# USB_Battery_Charging.net
KiCad netlist of a schematic drawn in Altium Designer
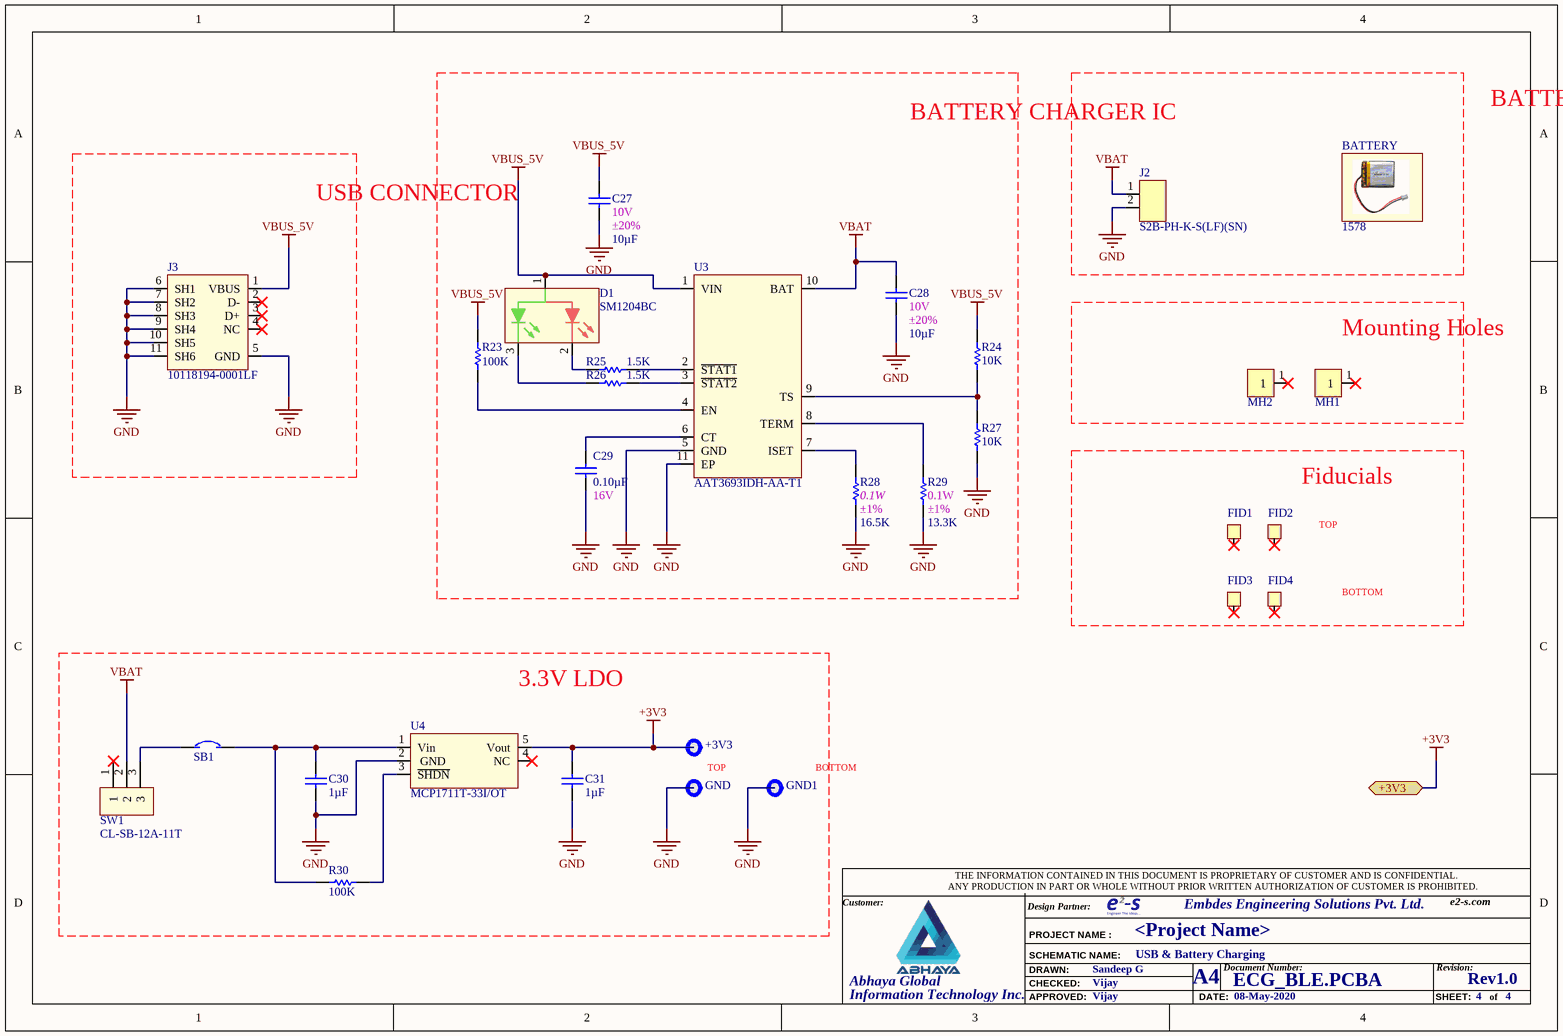
[diagram p0: USB & Battery Charging.SchDoc]

(export (version "E")
  (design (tool "Eeschema 10.0.6"))
  (components
    (comp (ref "+3V3")
      (value "TEST POINT")
      (footprint "TP_40X40")
      (fields (field (name "INTERNAL PART NUMBER") "EMS-TP40X40-S"))
      (libsource (lib "Integrated_Master_Library") (part "EMS-TP40X40-S"))
    )
    (comp (ref "BATTERY")
      (value "1578")
      (description "BATTERY LITHIUM 3.7V 500MAH")
      (fields
        (field (name "INTERNAL PART NUMBER") "EMS-1578")
        (field (name "MANUFACTURER") "Adafruit Industries LLC")
      )
      (libsource (lib "Master_ Library") (part "EMS-1578"))
    )
    (comp (ref "C27")
      (value "10µF")
      (footprint "SMDC0402")
      (description "CAP CER 10UF 10V X5R 0402")
      (fields
        (field (name "MANUFACTURER") "Samsung Electro-Mechanics America, Inc.")
        (field (name "MANUFACTURER PART NUMBER") "CL05A106MP5NUNC")
        (field (name "1ST AUXILIARY FIELD") "10V")
        (field (name "2ND AUXILIARY FIELD") "±20%")
      )
      (libsource (lib "Master_ Library") (part "ECA10U0M10V0-SB"))
    )
    (comp (ref "C28")
      (value "10µF")
      (footprint "SMDC0402")
      (description "CAP CER 10UF 10V X5R 0402")
      (fields
        (field (name "MANUFACTURER") "Samsung Electro-Mechanics America, Inc.")
        (field (name "MANUFACTURER PART NUMBER") "CL05A106MP5NUNC")
        (field (name "1ST AUXILIARY FIELD") "10V")
        (field (name "2ND AUXILIARY FIELD") "±20%")
      )
      (libsource (lib "Master_ Library") (part "ECA10U0M10V0-SB"))
    )
    (comp (ref "C29")
      (value "0.10µF")
      (footprint "SMDC0402")
      (description "CAP CER 0.1UF 16V X7R 0402")
      (fields
        (field (name "MANUFACTURER") "Samsung Electro-Mechanics America, Inc.")
        (field (name "MANUFACTURER PART NUMBER") "CL05B104KO5NNNC")
        (field (name "1ST AUXILIARY FIELD") "16V")
      )
      (libsource (lib "Master_ Library") (part "ECA0U10K16V0-1-SB"))
    )
    (comp (ref "C30")
      (value "1µF")
      (footprint "SMDC0402")
      (description "CAP CER 1UF 16V X5R 0402")
      (fields
        (field (name "MANUFACTURER") "Samsung Electro-Mechanics")
        (field (name "VENDOR PART NUMBER") "1276-1067-1-ND")
      )
      (libsource (lib "Integrated_Master_Library") (part "ECA1U00L16V0-SB"))
    )
    (comp (ref "C31")
      (value "1µF")
      (footprint "SMDC0402")
      (description "CAP CER 1UF 16V X5R 0402")
      (fields
        (field (name "MANUFACTURER") "Samsung Electro-Mechanics")
        (field (name "VENDOR PART NUMBER") "1276-1067-1-ND")
      )
      (libsource (lib "Integrated_Master_Library") (part "ECA1U00L16V0-SB"))
    )
    (comp (ref "D1")
      (value "SM1204BC")
      (footprint "LED-SM1204BC")
      (description "LED GREEN/RED CLEAR 1204 SMD R/A")
      (fields (field (name "MANUFACTURER") "Bivar Inc.") (field (name "VENDOR PART NUMBER") "492-1228-1-ND"))
      (libsource (lib "ECG_BLE") (part "ELDGR2V0020M0-S"))
    )
    (comp (ref "FID1")
      (value "FID40X40")
      (footprint "FID40X40")
      (libsource (lib "Integrated_Master_Library") (part "FID_40X40"))
    )
    (comp (ref "FID2")
      (value "FID40X40")
      (footprint "FID40X40")
      (libsource (lib "Integrated_Master_Library") (part "FID_40X40"))
    )
    (comp (ref "FID3")
      (value "FID40X40")
      (footprint "FID40X40")
      (libsource (lib "Integrated_Master_Library") (part "FID_40X40"))
    )
    (comp (ref "FID4")
      (value "FID40X40")
      (footprint "FID40X40")
      (libsource (lib "Integrated_Master_Library") (part "FID_40X40"))
    )
    (comp (ref "GND")
      (value "TEST POINT")
      (footprint "TP_40X40")
      (fields (field (name "INTERNAL PART NUMBER") "EMS-TP40X40-S"))
      (libsource (lib "Integrated_Master_Library") (part "EMS-TP40X40-S"))
    )
    (comp (ref "GND1")
      (value "TEST POINT")
      (footprint "TP_40X40")
      (fields (field (name "INTERNAL PART NUMBER") "EMS-TP40X40-S"))
      (libsource (lib "Integrated_Master_Library") (part "EMS-TP40X40-S"))
    )
    (comp (ref "J2")
      (value "S2B-PH-K-S(LF)(SN)")
      (footprint "SHDRRA2W70P0_200_1X2_590X790X550P")
      (description "CONN HOUSING PH 2POS 2MM WHITE")
      (fields
        (field (name "VENDOR PART NUMBER") "455-1719-ND")
        (field (name "MANUFACTURER") "JST Sales America Inc.")
      )
      (libsource (lib "Master_ Library") (part "ECNJSTHE02-T"))
    )
    (comp (ref "J3")
      (value "10118194-0001LF")
      (footprint "USB_MICRO_B_10118194-0001LF")
      (description "CONN USB MICRO B RECPT SMT R/A")
      (fields
        (field (name "MANUFACTURER") "Amphenol FCI")
        (field (name "INTERNAL PART NUMBER") "EINUSBBR06-S-1364")
      )
      (libsource (lib "Master_ Library") (part "EINUSBBR06-S-1364"))
    )
    (comp (ref "MH1")
      (value "Mounting hole")
      (footprint "MH_2P2MM_3P6KP")
      (fields (field (name "INTERNAL PART NUMBER") "EMS-MH2.2MM"))
      (libsource (lib "ECG_BLE") (part "EMS-MH2.2MM"))
    )
    (comp (ref "MH2")
      (value "Mounting hole")
      (footprint "MH_2P2MM_3P6KP")
      (fields (field (name "INTERNAL PART NUMBER") "EMS-MH2.2MM"))
      (libsource (lib "ECG_BLE") (part "EMS-MH2.2MM"))
    )
    (comp (ref "R23")
      (value "100K")
      (footprint "SMDRC0402")
      (description "RES SMD 100K OHM 1% 1/10W 0402")
      (fields
        (field (name "MANUFACTURER PART NUMBER") "ERJ-2RKF1003X")
        (field (name "MANUFACTURER") "Panasonic Electronic Components")
      )
      (libsource (lib "Master_ Library") (part "ERE100KG110-SB"))
    )
    (comp (ref "R24")
      (value "10K")
      (footprint "SMDR0402")
      (description "RES SMD 10K OHM 1% 1/10W 0402")
      (fields
        (field (name "MANUFACTURER") "Panasonic Electronic Components")
        (field (name "INTERNAL PART NUMBER") "ERE10K0G110-SB")
      )
      (libsource (lib "Master_ Library") (part "ERE10K0G110-SB"))
    )
    (comp (ref "R25")
      (value "1.5K")
      (footprint "SMDR0402")
      (description "RES SMD 1.5K OHM 1% 1/10W 0402")
      (fields
        (field (name "MANUFACTURER") "Panasonic Electronic Components")
        (field (name "INTERNAL PART NUMBER") "ERE1K50G110-SB")
      )
      (libsource (lib "Master_ Library") (part "ERE1K50G110-SB"))
    )
    (comp (ref "R26")
      (value "1.5K")
      (footprint "SMDR0402")
      (description "RES SMD 1.5K OHM 1% 1/10W 0402")
      (fields
        (field (name "MANUFACTURER") "Panasonic Electronic Components")
        (field (name "INTERNAL PART NUMBER") "ERE1K50G110-SB")
      )
      (libsource (lib "Master_ Library") (part "ERE1K50G110-SB"))
    )
    (comp (ref "R27")
      (value "10K")
      (footprint "SMDR0402")
      (description "RES SMD 10K OHM 1% 1/10W 0402")
      (fields
        (field (name "MANUFACTURER") "Panasonic Electronic Components")
        (field (name "INTERNAL PART NUMBER") "ERE10K0G110-SB")
      )
      (libsource (lib "Master_ Library") (part "ERE10K0G110-SB"))
    )
    (comp (ref "R28")
      (value "16.5K")
      (footprint "SMDR0402")
      (description "RES SMD 16.5K OHM 1% 1/10W 0402")
      (fields
        (field (name "MANUFACTURER PART NUMBER") "ERJ-2RKF1652X")
        (field (name "MANUFACTURER") "Panasonic Electronic Components")
        (field (name "1ST AUXILIARY FIELD") "0.1W")
        (field (name "2ND AUXILIARY FIELD") "±1%")
      )
      (libsource (lib "Master_ Library") (part "ERE16K5G110-SB"))
    )
    (comp (ref "R29")
      (value "13.3K")
      (footprint "SMDR0402")
      (description "RES SMD 13.3K OHM 1% 1/10W 0402")
      (fields
        (field (name "MANUFACTURER") "Panasonic Electronic Components")
        (field (name "INTERNAL PART NUMBER") "ERE13K3G110-SB")
        (field (name "1ST AUXILIARY FIELD") "0.1W")
        (field (name "2ND AUXILIARY FIELD") "±1%")
      )
      (libsource (lib "Master_ Library") (part "ERE13K3G110-SB"))
    )
    (comp (ref "R30")
      (value "100K")
      (footprint "SMDRC0402")
      (description "RES SMD 100K OHM 1% 1/10W 0402")
      (fields
        (field (name "MANUFACTURER PART NUMBER") "ERJ-2RKF1003X")
        (field (name "MANUFACTURER") "Panasonic Electronic Components")
      )
      (libsource (lib "Master_ Library") (part "ERE100KG110-SB"))
    )
    (comp (ref "SB1")
      (value "EMS_SB0805")
      (footprint "SB_0805")
      (libsource (lib "Masterlib_auto") (part "EMS_SB0805"))
    )
    (comp (ref "SW1")
      (value "CL-SB-12A-11T")
      (footprint "SWITCH_CLSB12A11T")
      (description "SWITCH SLIDE SPDT 200MA 12V")
      (fields
        (field (name "INTERNAL PART NUMBER") "EMS-CL-SB-12A-11T")
        (field (name "MANUFACTURER") "Nidec Copal Electronics")
      )
      (libsource (lib "ECG_BLE") (part "EMS-CL-SB-12A-11T"))
    )
    (comp (ref "U3")
      (value "AAT3693IDH-AA-T1")
      (footprint "SON40P220X220x80_HS-11N")
      (description "1.6A LINEAR LI-ION CHGR 10TDFN")
      (fields
        (field (name "INTERNAL PART NUMBER") "EICSSTDFN-10-1864")
        (field (name "MANUFACTURER") "Skyworks Solutions Inc.")
      )
      (libsource (lib "Master_ Library") (part "EICSSTDFN-10-1864"))
    )
    (comp (ref "U4")
      (value "IC REG LINEAR 3.3V 150MA SOT23-5")
      (footprint "SOT95P350X145-5N")
      (fields
        (field (name "INTERNAL PART NUMBER") "EICMTSOT23-5-****")
        (field (name "MANUFACTURER") "Microchip Technology")
        (field (name "VENDOR PART NUMBER") "MCP1711T-33I/OTCT-ND")
        (field (name "MANUFACTURER PART NUMBER") "MCP1711T-33I/OT")
      )
      (libsource (lib "ECG_BLE") (part "EICMTSOT23-5-****"))
    )
  )
  (nets
    (net (code "1") (name "+3V3") (class "Default")
      (node (ref "+3V3") (pin "1") (pinfunction "1_1") (pintype "passive"))
      (node (ref "C31") (pin "2") (pinfunction "2_2") (pintype "passive"))
      (node (ref "U4") (pin "5") (pinfunction "Vout_5") (pintype "passive"))
    )
    (net (code "2") (name "GND") (class "Default")
      (node (ref "C27") (pin "2") (pinfunction "2_2") (pintype "passive"))
      (node (ref "C28") (pin "2") (pinfunction "2_2") (pintype "passive"))
      (node (ref "C29") (pin "1") (pinfunction "1_1") (pintype "passive"))
      (node (ref "C30") (pin "1") (pinfunction "1_1") (pintype "passive"))
      (node (ref "C31") (pin "1") (pinfunction "1_1") (pintype "passive"))
      (node (ref "GND") (pin "1") (pinfunction "1_1") (pintype "passive"))
      (node (ref "GND1") (pin "1") (pinfunction "1_1") (pintype "passive"))
      (node (ref "J2") (pin "2") (pintype "passive"))
      (node (ref "J3") (pin "10") (pinfunction "SH5_10") (pintype "passive"))
      (node (ref "J3") (pin "11") (pinfunction "SH6_11") (pintype "passive"))
      (node (ref "J3") (pin "5") (pinfunction "GND_5") (pintype "passive"))
      (node (ref "J3") (pin "6") (pinfunction "SH1_6") (pintype "passive"))
      (node (ref "J3") (pin "7") (pinfunction "SH2_7") (pintype "passive"))
      (node (ref "J3") (pin "8") (pinfunction "SH3_8") (pintype "passive"))
      (node (ref "J3") (pin "9") (pinfunction "SH4_9") (pintype "passive"))
      (node (ref "R27") (pin "2") (pinfunction "2_2") (pintype "passive"))
      (node (ref "R28") (pin "1") (pinfunction "1_1") (pintype "passive"))
      (node (ref "R29") (pin "2") (pinfunction "2_2") (pintype "passive"))
      (node (ref "U3") (pin "11") (pinfunction "EP_11") (pintype "passive"))
      (node (ref "U3") (pin "5") (pinfunction "GND_5") (pintype "passive"))
      (node (ref "U4") (pin "2") (pinfunction "GND_2") (pintype "power_in"))
    )
    (net (code "3") (name "Net-(D1-K-Pad2)") (class "Default")
      (node (ref "D1") (pin "2") (pinfunction "K_2") (pintype "passive"))
      (node (ref "R25") (pin "2") (pinfunction "2_2") (pintype "passive"))
    )
    (net (code "4") (name "Net-(D1-K-Pad3)") (class "Default")
      (node (ref "D1") (pin "3") (pinfunction "K_3") (pintype "passive"))
      (node (ref "R26") (pin "2") (pinfunction "2_2") (pintype "passive"))
    )
    (net (code "5") (name "Net-(SB1-Pad1)") (class "Default")
      (node (ref "SB1") (pin "1") (pinfunction "1_1") (pintype "passive"))
      (node (ref "SW1") (pin "3") (pinfunction "3_3") (pintype "passive"))
    )
    (net (code "6") (name "Net-(U3-CT)") (class "Default")
      (node (ref "C29") (pin "2") (pinfunction "2_2") (pintype "passive"))
      (node (ref "U3") (pin "6") (pinfunction "CT_6") (pintype "passive"))
    )
    (net (code "7") (name "Net-(U3-EN)") (class "Default")
      (node (ref "R23") (pin "2") (pinfunction "2_2") (pintype "passive"))
      (node (ref "U3") (pin "4") (pinfunction "EN_4") (pintype "passive"))
    )
    (net (code "8") (name "Net-(U3-ISET)") (class "Default")
      (node (ref "R28") (pin "2") (pinfunction "2_2") (pintype "passive"))
      (node (ref "U3") (pin "7") (pinfunction "ISET_7") (pintype "passive"))
    )
    (net (code "9") (name "Net-(U3-TERM)") (class "Default")
      (node (ref "R29") (pin "1") (pinfunction "1_1") (pintype "passive"))
      (node (ref "U3") (pin "8") (pinfunction "TERM_8") (pintype "passive"))
    )
    (net (code "10") (name "Net-(U3-TS)") (class "Default")
      (node (ref "R24") (pin "2") (pinfunction "2_2") (pintype "passive"))
      (node (ref "R27") (pin "1") (pinfunction "1_1") (pintype "passive"))
      (node (ref "U3") (pin "9") (pinfunction "TS_9") (pintype "passive"))
    )
    (net (code "11") (name "Net-(U3-~{STAT1})") (class "Default")
      (node (ref "R25") (pin "1") (pinfunction "1_1") (pintype "passive"))
      (node (ref "U3") (pin "2") (pinfunction "~{STAT1}_2") (pintype "passive"))
    )
    (net (code "12") (name "Net-(U3-~{STAT2})") (class "Default")
      (node (ref "R26") (pin "1") (pinfunction "1_1") (pintype "passive"))
      (node (ref "U3") (pin "3") (pinfunction "~{STAT2}_3") (pintype "passive"))
    )
    (net (code "13") (name "Net-(U4-Vin)") (class "Default")
      (node (ref "C30") (pin "2") (pinfunction "2_2") (pintype "passive"))
      (node (ref "R30") (pin "2") (pinfunction "2_2") (pintype "passive"))
      (node (ref "SB1") (pin "2") (pinfunction "2_2") (pintype "passive"))
      (node (ref "U4") (pin "1") (pinfunction "Vin_1") (pintype "passive"))
    )
    (net (code "14") (name "Net-(U4-~{SHDN})") (class "Default")
      (node (ref "R30") (pin "1") (pinfunction "1_1") (pintype "passive"))
      (node (ref "U4") (pin "3") (pinfunction "~{SHDN}_3") (pintype "passive"))
    )
    (net (code "15") (name "VBAT") (class "Default")
      (node (ref "C28") (pin "1") (pinfunction "1_1") (pintype "passive"))
      (node (ref "J2") (pin "1") (pintype "passive"))
      (node (ref "SW1") (pin "2") (pinfunction "2_2") (pintype "passive"))
      (node (ref "U3") (pin "10") (pinfunction "BAT_10") (pintype "passive"))
    )
    (net (code "16") (name "VBUS_5V") (class "Default")
      (node (ref "C27") (pin "1") (pinfunction "1_1") (pintype "passive"))
      (node (ref "D1") (pin "1") (pinfunction "A_1") (pintype "passive"))
      (node (ref "J3") (pin "1") (pinfunction "VBUS_1") (pintype "passive"))
      (node (ref "R23") (pin "1") (pinfunction "1_1") (pintype "passive"))
      (node (ref "R24") (pin "1") (pinfunction "1_1") (pintype "passive"))
      (node (ref "U3") (pin "1") (pinfunction "VIN_1") (pintype "passive"))
    )
    (net (code "17") (name "unconnected-(FID1-Pad0)") (class "Default")
      (node (ref "FID1") (pin "0") (pinfunction "0_0") (pintype "passive+no_connect"))
    )
    (net (code "18") (name "unconnected-(FID2-Pad0)") (class "Default")
      (node (ref "FID2") (pin "0") (pinfunction "0_0") (pintype "passive+no_connect"))
    )
    (net (code "19") (name "unconnected-(FID3-Pad0)") (class "Default")
      (node (ref "FID3") (pin "0") (pinfunction "0_0") (pintype "passive+no_connect"))
    )
    (net (code "20") (name "unconnected-(FID4-Pad0)") (class "Default")
      (node (ref "FID4") (pin "0") (pinfunction "0_0") (pintype "passive+no_connect"))
    )
    (net (code "21") (name "unconnected-(J3-D+-Pad3)") (class "Default")
      (node (ref "J3") (pin "3") (pinfunction "D+_3") (pintype "passive+no_connect"))
    )
    (net (code "22") (name "unconnected-(J3-D--Pad2)") (class "Default")
      (node (ref "J3") (pin "2") (pinfunction "D-_2") (pintype "passive+no_connect"))
    )
    (net (code "23") (name "unconnected-(J3-NC-Pad4)") (class "Default")
      (node (ref "J3") (pin "4") (pinfunction "NC_4") (pintype "passive+no_connect"))
    )
    (net (code "24") (name "unconnected-(MH1-Pad1)") (class "Default")
      (node (ref "MH1") (pin "1") (pinfunction "1_1") (pintype "passive+no_connect"))
    )
    (net (code "25") (name "unconnected-(MH2-Pad1)") (class "Default")
      (node (ref "MH2") (pin "1") (pinfunction "1_1") (pintype "passive+no_connect"))
    )
    (net (code "26") (name "unconnected-(SW1-Pad1)") (class "Default")
      (node (ref "SW1") (pin "1") (pinfunction "1_1") (pintype "passive+no_connect"))
    )
    (net (code "27") (name "unconnected-(U4-NC-Pad4)") (class "Default")
      (node (ref "U4") (pin "4") (pinfunction "NC_4") (pintype "passive+no_connect"))
    )
  )
)
